# DIO45_TOP.net
KiCad netlist of a schematic drawn in Altium Designer
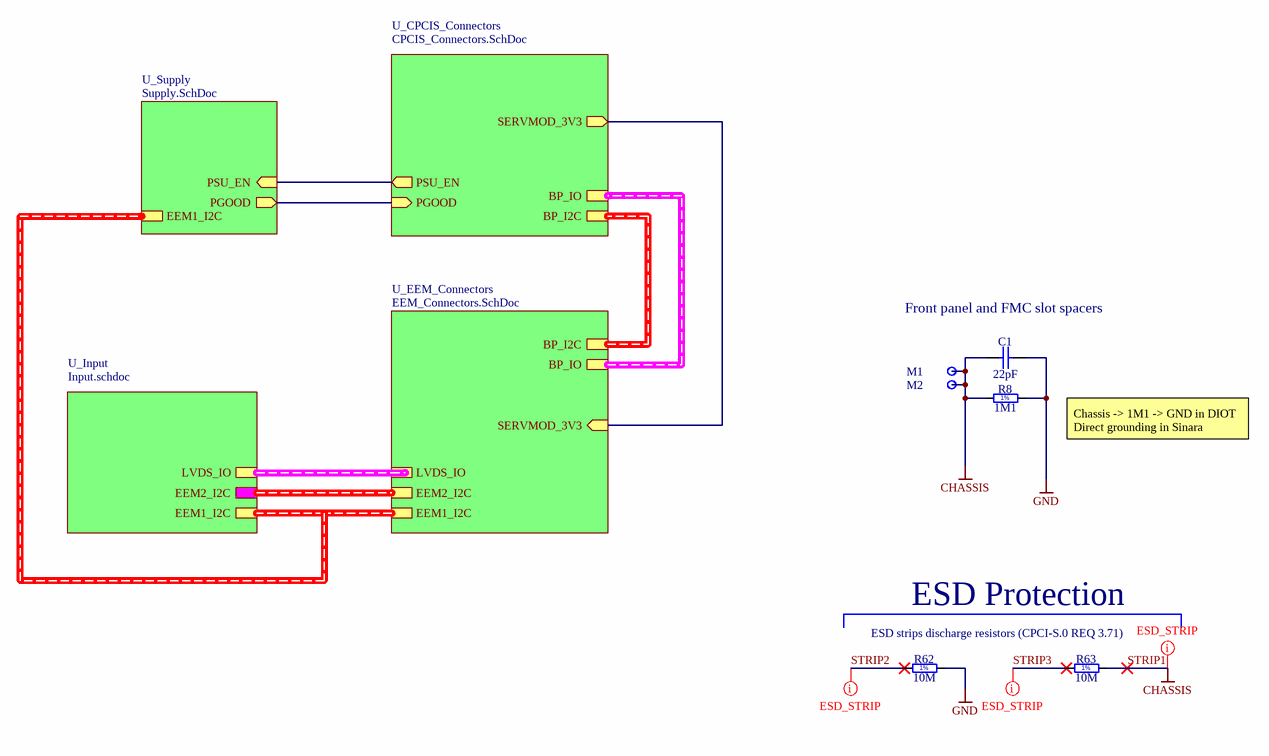
[diagram p0: DIO45_TOP.SchDoc]

(export (version "E")
  (design (tool "Eeschema 10.0.6"))
  (components
    (comp (ref "C1")
      (value "22pF")
      (footprint "CAPC1005X55N")
      (description "Non-polarised capacitor")
      (fields
        (field (name "PART NUMBER") "CC0402_22PF_50V_5%_C0G")
        (field (name "VOLTAGE") "50V")
        (field (name "AUTHOR") "CERN DEM JLC")
      )
      (libsource (lib "Capacitors") (part "Capacitor - non polarized"))
    )
    (comp (ref "M1")
      (value "Plated Hole")
      (footprint "MTG300_600")
      (description "Single Terminal Socket")
      (fields (field (name "PART NUMBER") "PLATED_HOLE3.0_PAD6.0") (field (name "AUTHOR") "CERN DEM JLC"))
      (libsource (lib "Eletro-mechanical") (part "Single Terminal Socket"))
    )
    (comp (ref "M2")
      (value "Plated Hole")
      (footprint "MTG300_600")
      (description "Single Terminal Socket")
      (fields (field (name "PART NUMBER") "PLATED_HOLE3.0_PAD6.0") (field (name "AUTHOR") "CERN DEM JLC"))
      (libsource (lib "Eletro-mechanical") (part "Single Terminal Socket"))
    )
    (comp (ref "R8")
      (value "1M1")
      (footprint "RESC2012X60N")
      (description "Resistor - 1%")
      (fields
        (field (name "PART NUMBER") "R0805_1M1_1%_0.125W_100PPM")
        (field (name "MANUFACTURER") "GENERIC")
        (field (name "AUTHOR") "CERN DEM JLC")
      )
      (libsource (lib "Resistors") (part "Resistor - 1%"))
    )
    (comp (ref "R62")
      (value "10M")
      (footprint "RESC2113X55N")
      (description "Resistor - 1%")
      (fields
        (field (name "PART NUMBER") "R0805_10M_1%_0.125W_100PPM_VISHAY_CRCW e3")
        (field (name "POWER") "0.125W")
        (field (name "AUTHOR") "CERN DEM BC")
      )
      (libsource (lib "Resistors") (part "Resistor - 1%"))
    )
    (comp (ref "R63")
      (value "10M")
      (footprint "RESC2113X55N")
      (description "Resistor - 1%")
      (fields
        (field (name "PART NUMBER") "R0805_10M_1%_0.125W_100PPM_VISHAY_CRCW e3")
        (field (name "POWER") "0.125W")
        (field (name "AUTHOR") "CERN DEM BC")
      )
      (libsource (lib "Resistors") (part "Resistor - 1%"))
    )
  )
  (nets
    (net (code "10") (name "/STRIP2") (class "Default")
      (node (ref "R62") (pin "1") (pinfunction "1_1") (pintype "passive+no_connect"))
    )
    (net (code "11") (name "/STRIP3") (class "Default")
      (node (ref "R63") (pin "1") (pinfunction "1_1") (pintype "passive+no_connect"))
    )
    (net (code "12") (name "CHASSIS") (class "Default")
      (node (ref "C1") (pin "1") (pinfunction "1_1") (pintype "passive"))
      (node (ref "M1") (pin "1") (pinfunction "1_1") (pintype "bidirectional"))
      (node (ref "M2") (pin "1") (pinfunction "1_1") (pintype "bidirectional"))
      (node (ref "R63") (pin "2") (pinfunction "2_2") (pintype "passive"))
      (node (ref "R8") (pin "1") (pinfunction "1_1") (pintype "passive"))
    )
    (net (code "13") (name "GND") (class "Default")
      (node (ref "C1") (pin "2") (pinfunction "2_2") (pintype "passive"))
      (node (ref "R62") (pin "2") (pinfunction "2_2") (pintype "passive"))
      (node (ref "R8") (pin "2") (pinfunction "2_2") (pintype "passive"))
    )
  )
)
